# usb-wifi-adapter-box.net
KiCad netlist of a schematic drawn in EAGLE
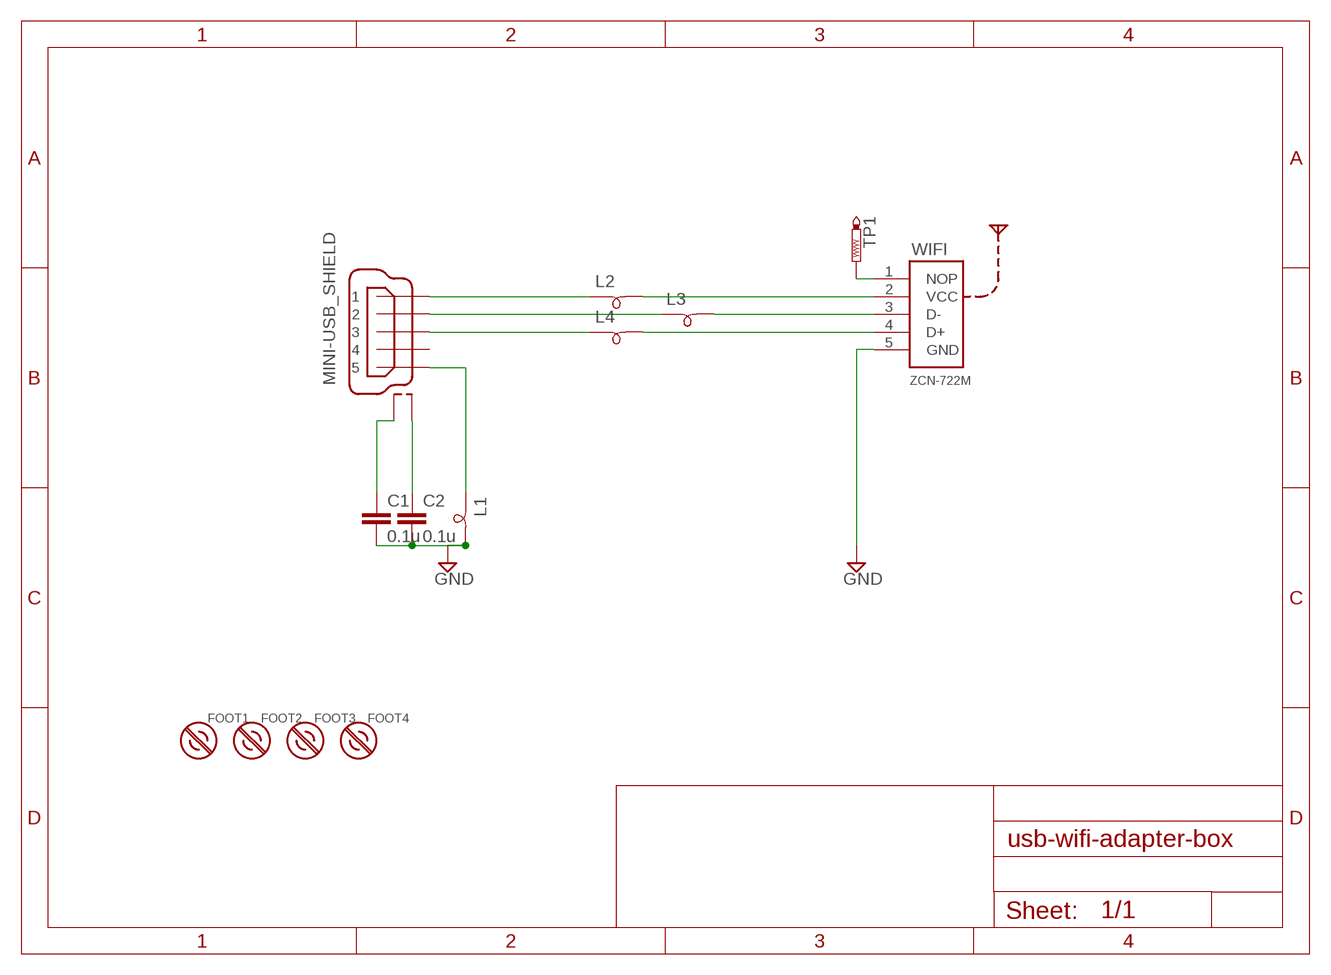
[diagram p0: schematic, sheet 1]

(export (version "E")
  (design (tool "Eeschema 10.0.6"))
  (components
    (comp (ref "C1")
      (value "0.1u")
      (footprint "eagle-import:C0805")
      (libsource (lib "eagle-import") (part "C-EUC0805"))
    )
    (comp (ref "C2")
      (value "0.1u")
      (footprint "eagle-import:C0805")
      (libsource (lib "eagle-import") (part "C-EUC0805"))
    )
    (comp (ref "CONN1")
      (value "MINI-USB_SHIELD")
      (footprint "eagle-import:RUGGEDUSB")
      (libsource (lib "eagle-import") (part "MINI-USB_SHIELD"))
    )
    (comp (ref "FOOT1")
      (value "_4-BARE_MOUNTING_HOLE/.400")
      (footprint "eagle-import:_4_.400-BARE+STD_TOOL_CLEARANCE")
      (libsource (lib "eagle-import") (part "_4-BARE_MOUNTING_HOLE/.400"))
    )
    (comp (ref "FOOT2")
      (value "_4-BARE_MOUNTING_HOLE/.400")
      (footprint "eagle-import:_4_.400-BARE+STD_TOOL_CLEARANCE")
      (libsource (lib "eagle-import") (part "_4-BARE_MOUNTING_HOLE/.400"))
    )
    (comp (ref "FOOT3")
      (value "_4-BARE_MOUNTING_HOLE/.400")
      (footprint "eagle-import:_4_.400-BARE+STD_TOOL_CLEARANCE")
      (libsource (lib "eagle-import") (part "_4-BARE_MOUNTING_HOLE/.400"))
    )
    (comp (ref "FOOT4")
      (value "_4-BARE_MOUNTING_HOLE/.400")
      (footprint "eagle-import:_4_.400-BARE+STD_TOOL_CLEARANCE")
      (libsource (lib "eagle-import") (part "_4-BARE_MOUNTING_HOLE/.400"))
    )
    (comp (ref "L1")
      (value "INDUCTOR-BEAD")
      (footprint "eagle-import:R0805")
      (libsource (lib "eagle-import") (part "INDUCTOR-BEAD"))
    )
    (comp (ref "L2")
      (value "INDUCTOR-BEAD")
      (footprint "eagle-import:R0805")
      (libsource (lib "eagle-import") (part "INDUCTOR-BEAD"))
    )
    (comp (ref "L3")
      (value "INDUCTOR-BEAD")
      (footprint "eagle-import:R0805")
      (libsource (lib "eagle-import") (part "INDUCTOR-BEAD"))
    )
    (comp (ref "L4")
      (value "INDUCTOR-BEAD")
      (footprint "eagle-import:R0805")
      (libsource (lib "eagle-import") (part "INDUCTOR-BEAD"))
    )
    (comp (ref "TP1")
      (value "PTR1PAD1-13")
      (footprint "eagle-import:P1-13")
      (libsource (lib "eagle-import") (part "PTR1PAD1-13"))
    )
    (comp (ref "WIFI")
      (value "ZCN-722M")
      (footprint "eagle-import:ZCN-722M")
      (libsource (lib "eagle-import") (part "ZCN-722M"))
    )
  )
  (nets
    (net (code "1") (name "GND") (class "Default")
      (node (ref "C1") (pin "2") (pinfunction "2_2") (pintype "passive"))
      (node (ref "C2") (pin "2") (pinfunction "2_2") (pintype "passive"))
      (node (ref "L1") (pin "2") (pinfunction "2_2") (pintype "passive"))
      (node (ref "WIFI") (pin "5") (pinfunction "GND_5") (pintype "bidirectional"))
    )
    (net (code "2") (name "Net-(CONN1-Pad1)") (class "Default")
      (node (ref "CONN1") (pin "1") (pinfunction "1_1") (pintype "passive"))
      (node (ref "L2") (pin "1") (pinfunction "1_1") (pintype "passive"))
    )
    (net (code "3") (name "Net-(CONN1-Pad2)") (class "Default")
      (node (ref "CONN1") (pin "2") (pinfunction "2_2") (pintype "passive"))
      (node (ref "L3") (pin "1") (pinfunction "1_1") (pintype "passive"))
    )
    (net (code "4") (name "Net-(CONN1-Pad3)") (class "Default")
      (node (ref "CONN1") (pin "3") (pinfunction "3_3") (pintype "passive"))
      (node (ref "L4") (pin "1") (pinfunction "1_1") (pintype "passive"))
    )
    (net (code "5") (name "Net-(CONN1-Pad5)") (class "Default")
      (node (ref "CONN1") (pin "5") (pinfunction "5_5") (pintype "passive"))
      (node (ref "L1") (pin "1") (pinfunction "1_1") (pintype "passive"))
    )
    (net (code "6") (name "Net-(CONN1B-S1)") (class "Default")
      (node (ref "C1") (pin "1") (pinfunction "1_1") (pintype "passive"))
      (node (ref "CONN1") (pin "SHLD@1") (pinfunction "S1_SHLD@1") (pintype "passive"))
    )
    (net (code "7") (name "Net-(CONN1B-S2)") (class "Default")
      (node (ref "C2") (pin "1") (pinfunction "1_1") (pintype "passive"))
      (node (ref "CONN1") (pin "SHLD@2") (pinfunction "S2_SHLD@2") (pintype "passive"))
    )
    (net (code "8") (name "Net-(WIFI-D+)") (class "Default")
      (node (ref "L4") (pin "2") (pinfunction "2_2") (pintype "passive"))
      (node (ref "WIFI") (pin "4") (pinfunction "D+_4") (pintype "bidirectional"))
    )
    (net (code "9") (name "Net-(WIFI-D-)") (class "Default")
      (node (ref "L3") (pin "2") (pinfunction "2_2") (pintype "passive"))
      (node (ref "WIFI") (pin "3") (pinfunction "D-_3") (pintype "bidirectional"))
    )
    (net (code "10") (name "Net-(WIFI-NOP)") (class "Default")
      (node (ref "TP1") (pin "TP") (pinfunction "TP_TP") (pintype "input"))
      (node (ref "WIFI") (pin "1") (pinfunction "NOP_1") (pintype "bidirectional"))
    )
    (net (code "11") (name "Net-(WIFI-VCC)") (class "Default")
      (node (ref "L2") (pin "2") (pinfunction "2_2") (pintype "passive"))
      (node (ref "WIFI") (pin "2") (pinfunction "VCC_2") (pintype "bidirectional"))
    )
    (net (code "12") (name "unconnected-(CONN1-Pad4)") (class "Default")
      (node (ref "CONN1") (pin "4") (pinfunction "4_4") (pintype "passive"))
    )
  )
)
